# board.net
KiCad netlist of a schematic drawn in EAGLE
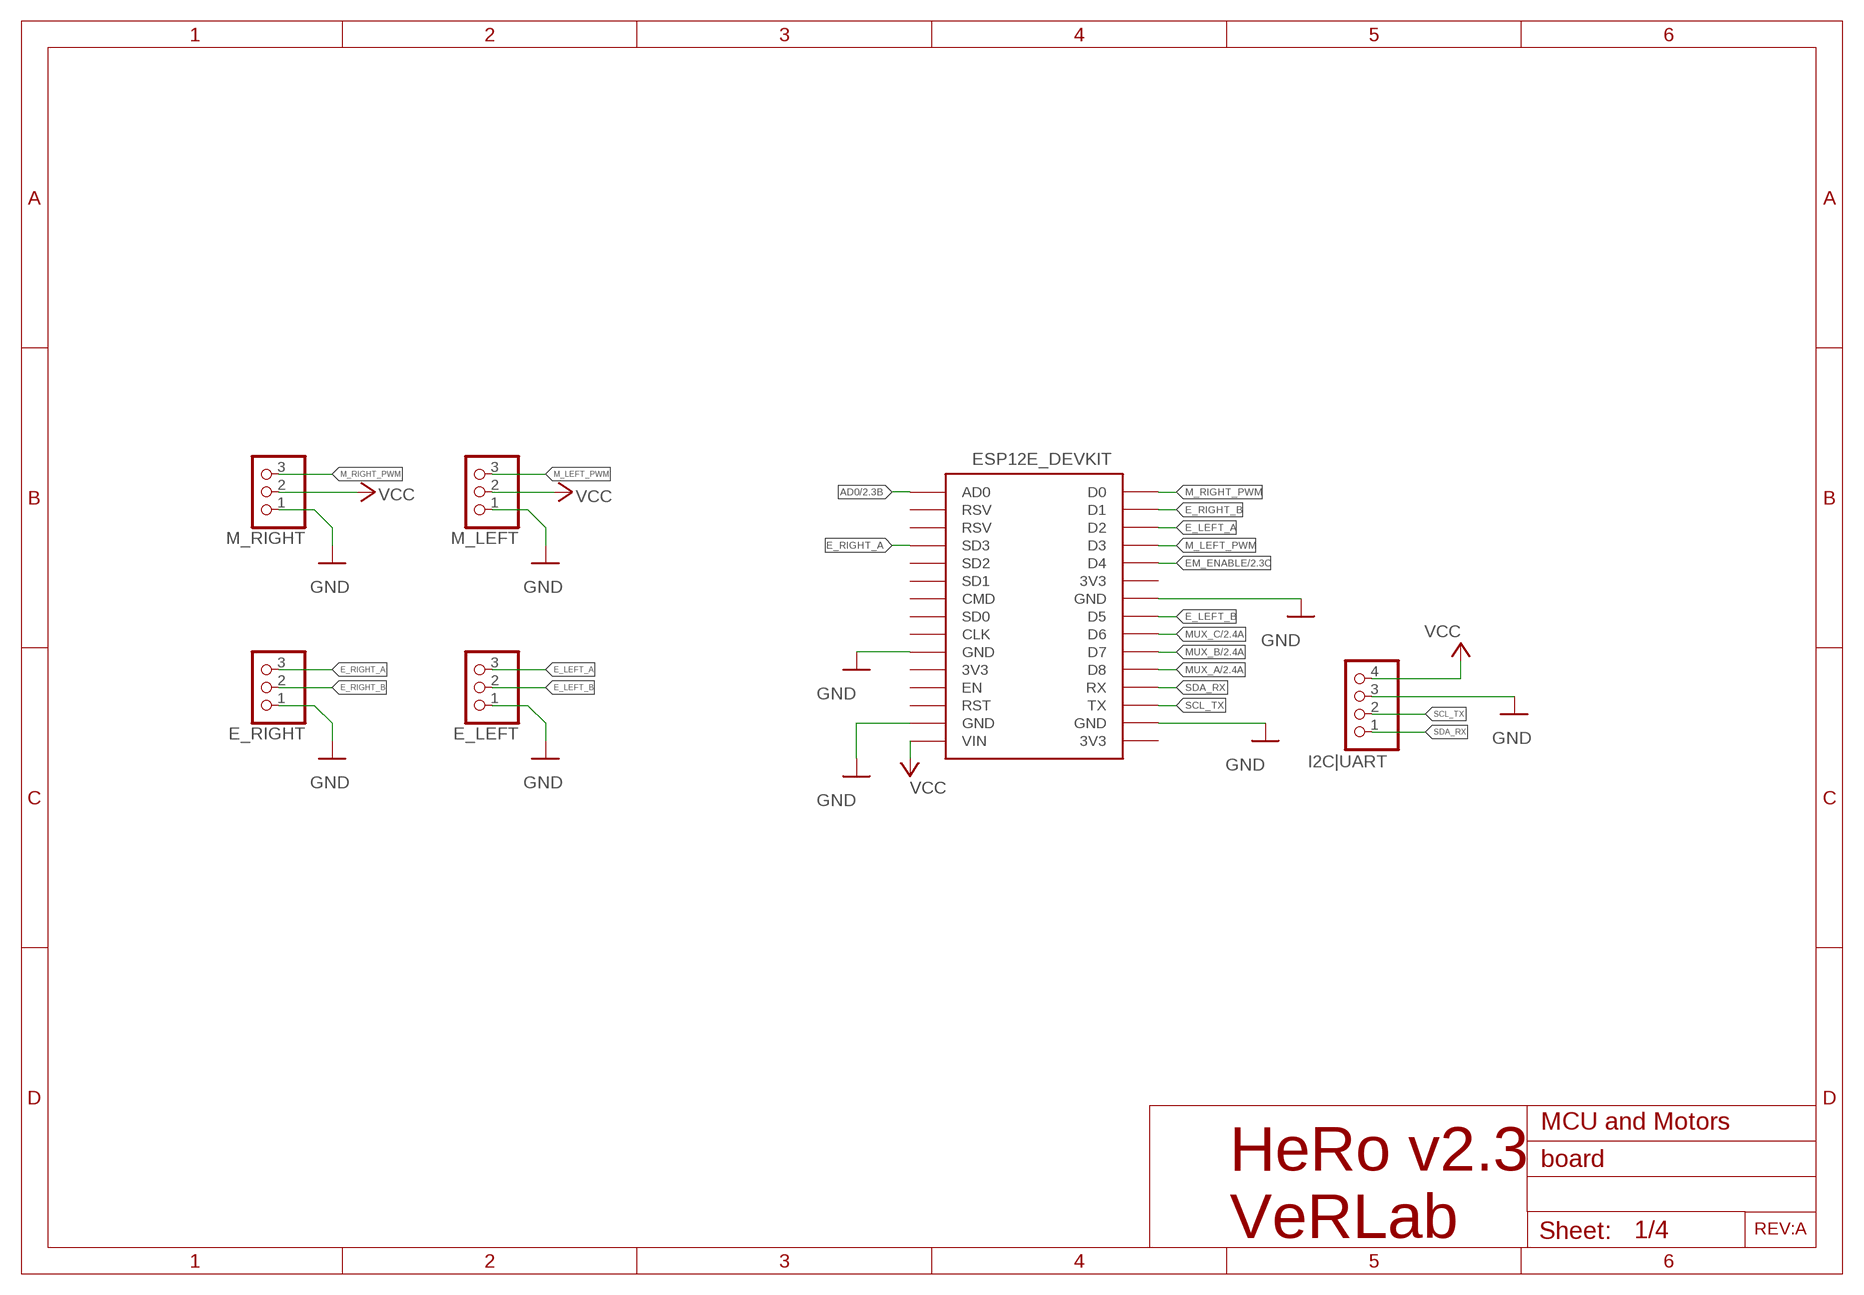
[diagram p0: schematic, sheet 1]
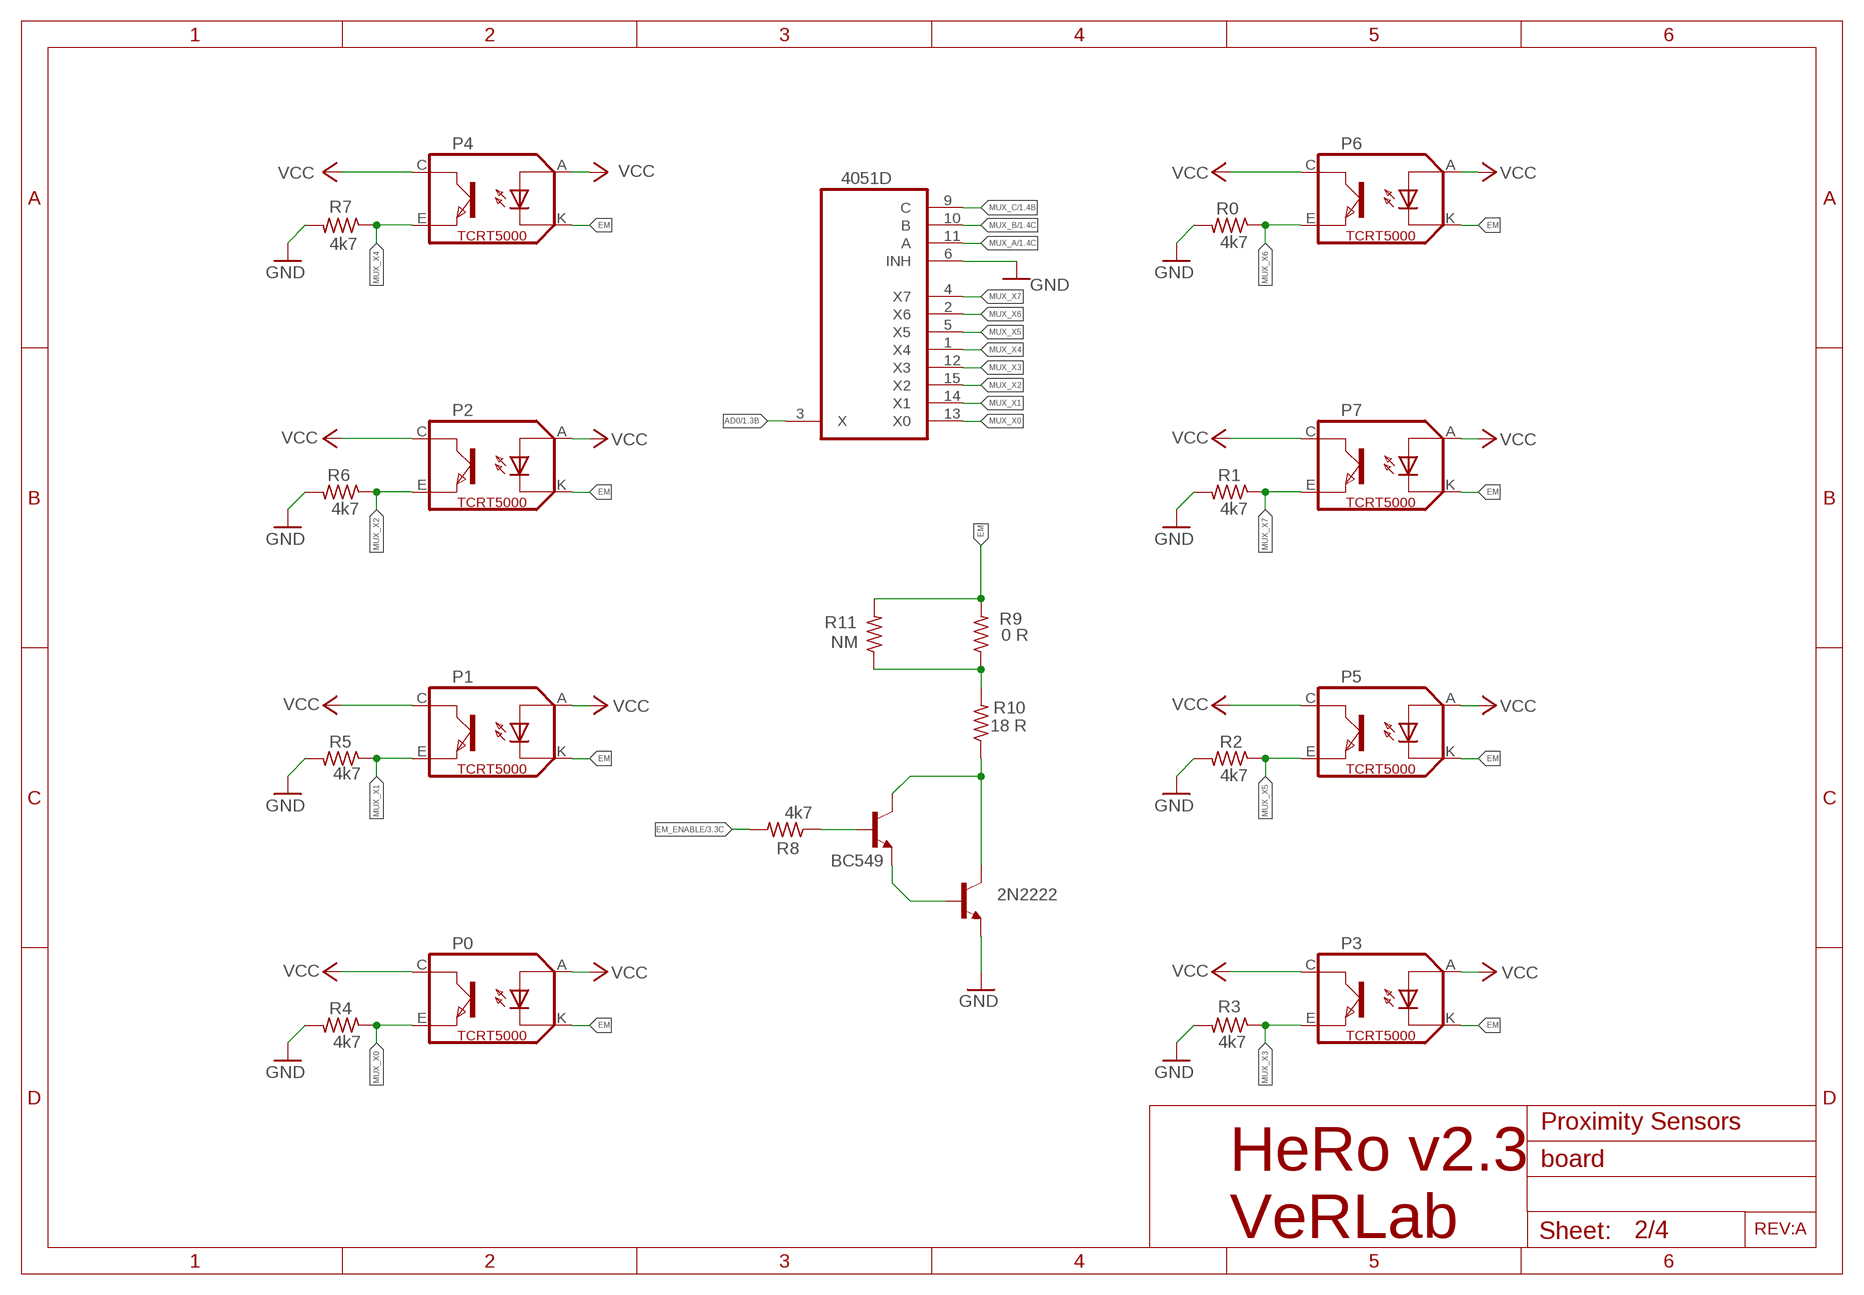
[diagram p1: schematic, sheet 2]
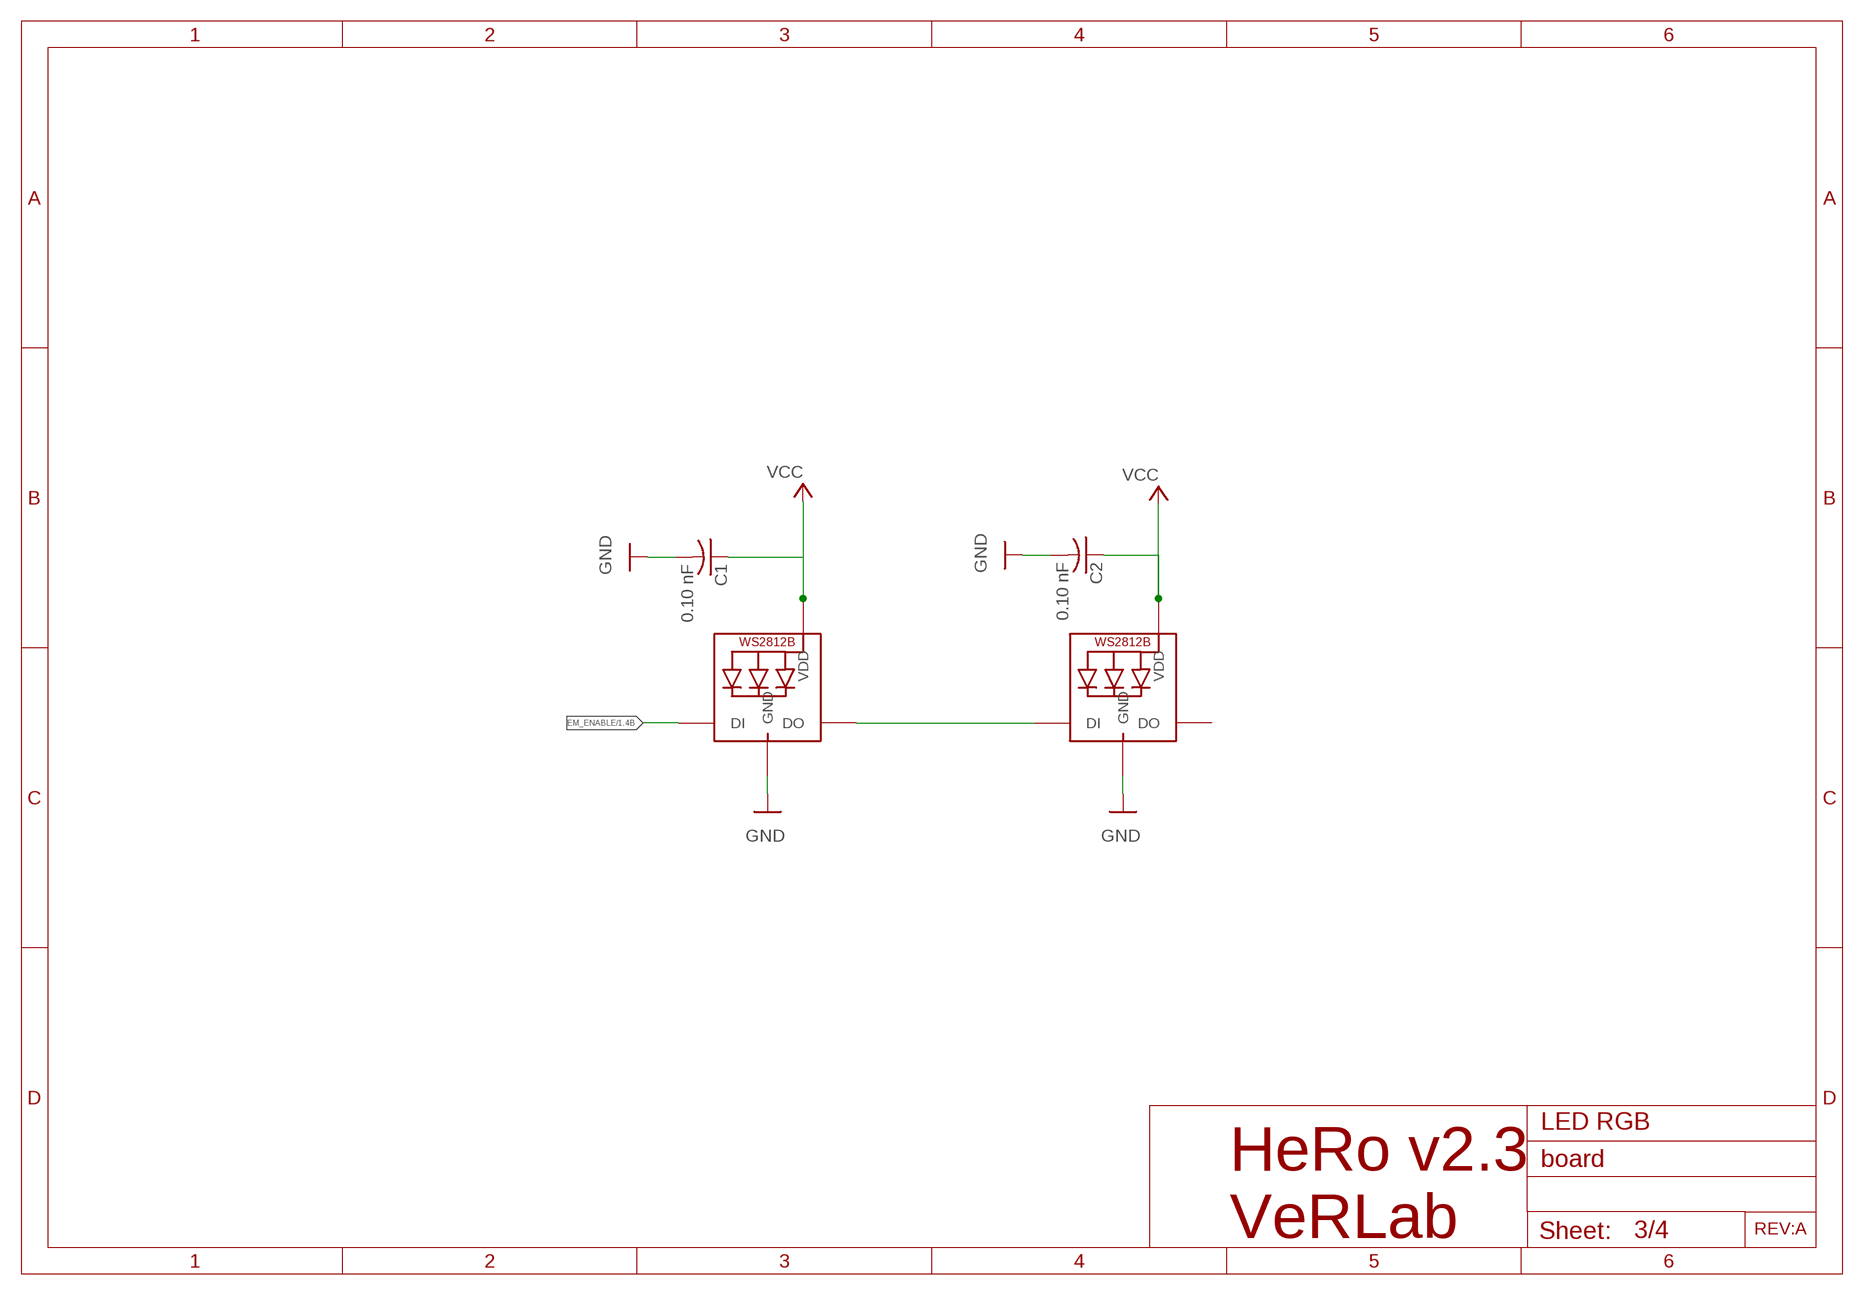
[diagram p2: schematic, sheet 3]
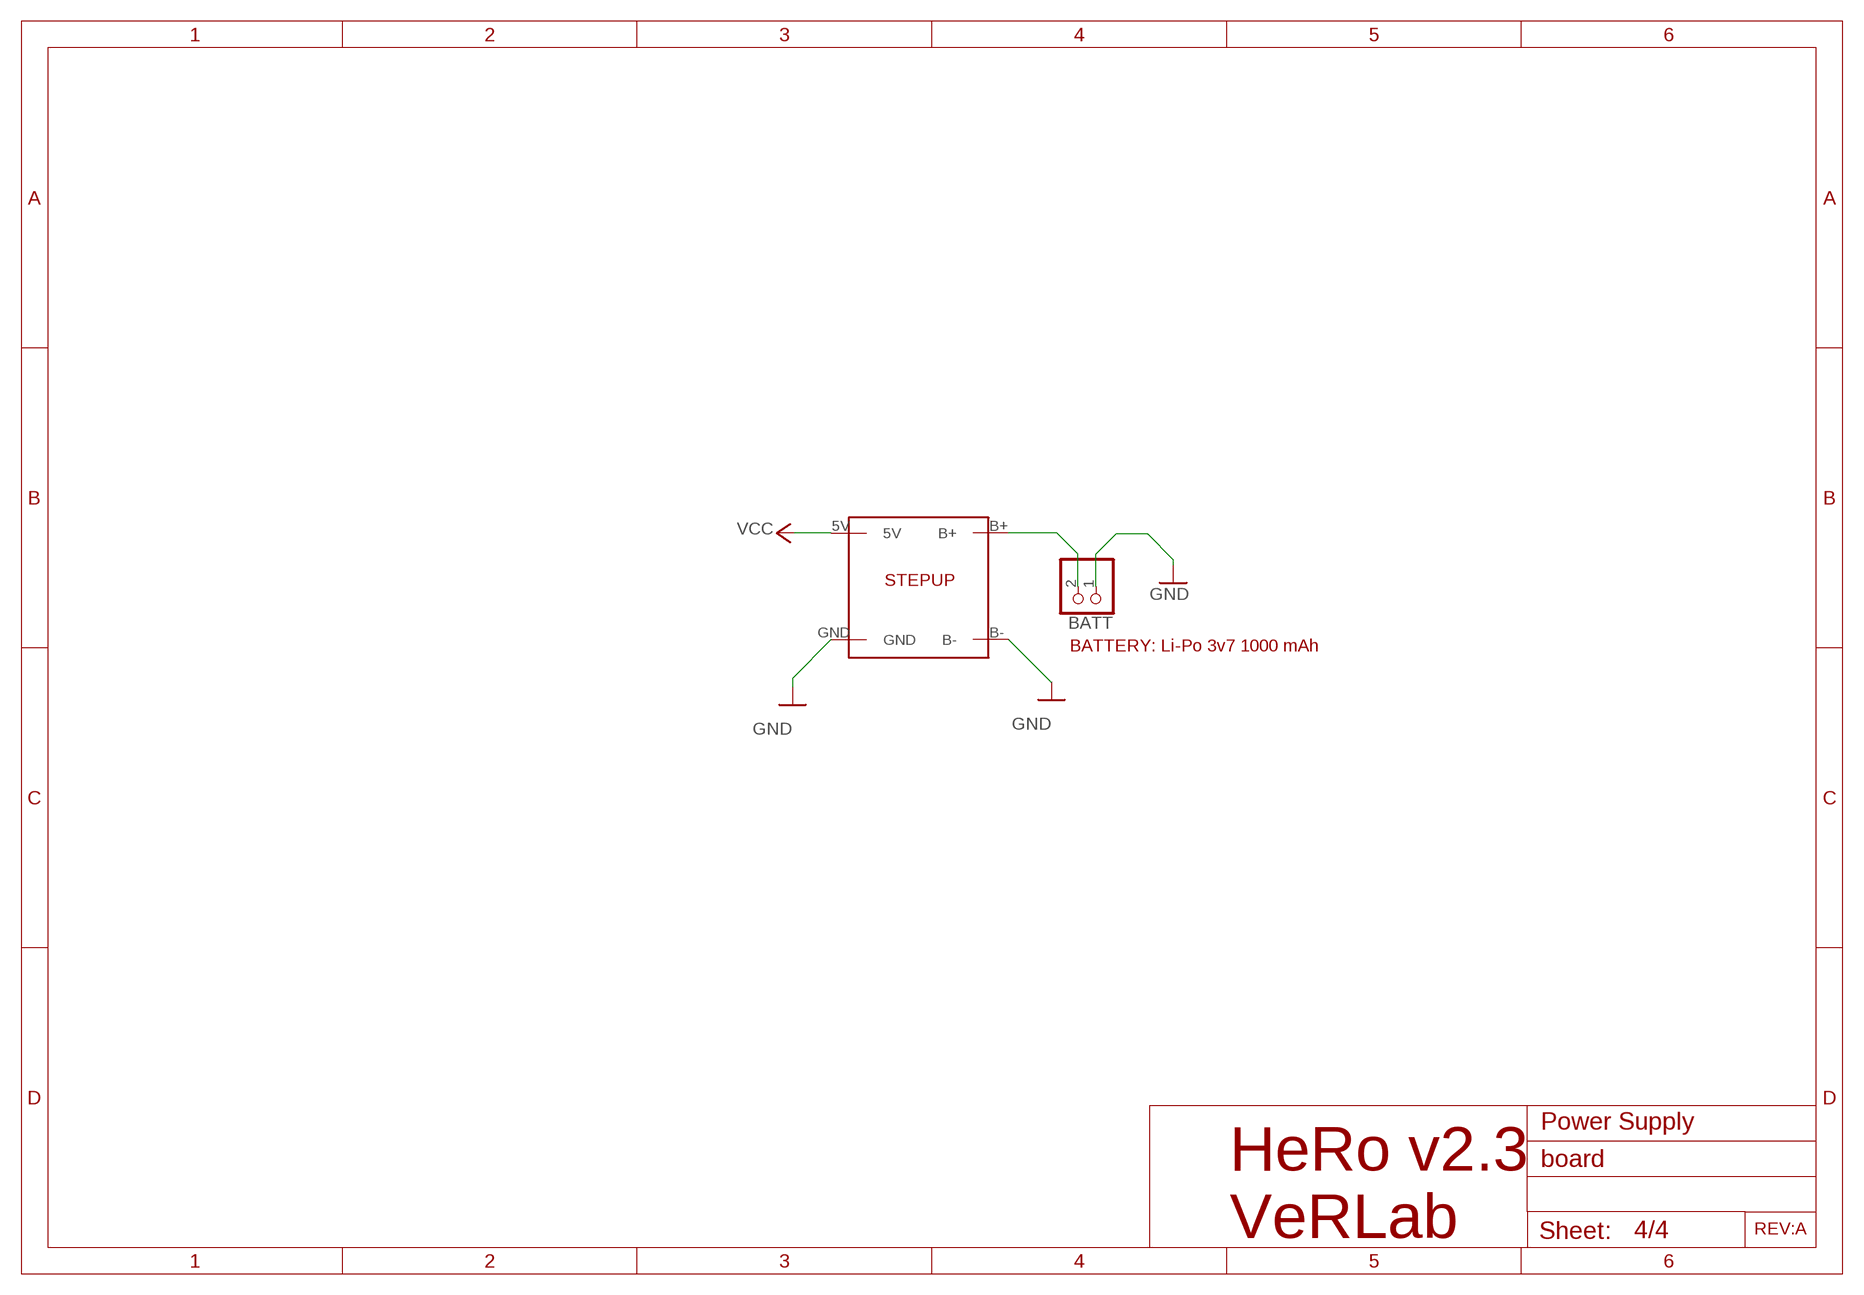
[diagram p3: schematic, sheet 4]

(export (version "E")
  (design (tool "Eeschema 10.0.6"))
  (components
    (comp (ref "E_LEFT")
      (value "PINHD-1X3")
      (footprint "eagle-import:1X03")
      (libsource (lib "eagle-import") (part "PINHD-1X3"))
    )
    (comp (ref "E_RIGHT")
      (value "PINHD-1X3")
      (footprint "eagle-import:1X03")
      (libsource (lib "eagle-import") (part "PINHD-1X3"))
    )
    (comp (ref "I2C|UART")
      (value "PINHD-1X4")
      (footprint "eagle-import:1X04")
      (libsource (lib "eagle-import") (part "PINHD-1X4"))
    )
    (comp (ref "M_LEFT")
      (value "PINHD-1X3")
      (footprint "eagle-import:1X03")
      (libsource (lib "eagle-import") (part "PINHD-1X3"))
    )
    (comp (ref "M_RIGHT")
      (value "PINHD-1X3")
      (footprint "eagle-import:1X03")
      (libsource (lib "eagle-import") (part "PINHD-1X3"))
    )
    (comp (ref "U$1")
      (value "ESP12E_DEVKIT")
      (footprint "eagle-import:ESP12E_DEVKIT")
      (libsource (lib "eagle-import") (part "ESP12E_DEVKIT"))
    )
    (comp (ref "C1")
      (value "0.10 nF")
      (footprint "eagle-import:C0603")
      (libsource (lib "eagle-import") (part "C-USC0603"))
    )
    (comp (ref "C2")
      (value "0.10 nF")
      (footprint "eagle-import:C0603")
      (libsource (lib "eagle-import") (part "C-USC0603"))
    )
    (comp (ref "LED3")
      (value "WS2812B5050")
      (footprint "eagle-import:WS2812B")
      (libsource (lib "eagle-import") (part "WS2812B5050"))
    )
    (comp (ref "LED4")
      (value "WS2812B5050")
      (footprint "eagle-import:WS2812B")
      (libsource (lib "eagle-import") (part "WS2812B5050"))
    )
    (comp (ref "BATT")
      (value "PINHD-1X2")
      (footprint "eagle-import:1X02")
      (libsource (lib "eagle-import") (part "PINHD-1X2"))
    )
    (comp (ref "OS1")
      (value "STEPUP")
      (footprint "eagle-import:STEPUP")
      (libsource (lib "eagle-import") (part "STEPUP"))
    )
    (comp (ref "BC549")
      (value "BC549-NPN-TO92-CBE")
      (footprint "eagle-import:TO92-CBE")
      (fields (field (name "SPICEPREFIX") "J"))
      (libsource (lib "eagle-import") (part "-NPN-TO92-CBEBC549"))
    )
    (comp (ref "IC2")
      (value "4051D")
      (footprint "eagle-import:SO16")
      (libsource (lib "eagle-import") (part "4051D"))
    )
    (comp (ref "P0")
      (value "TCRT5000")
      (footprint "eagle-import:TCRT5000")
      (libsource (lib "eagle-import") (part "TCRT5000"))
    )
    (comp (ref "P1")
      (value "TCRT5000")
      (footprint "eagle-import:TCRT5000")
      (libsource (lib "eagle-import") (part "TCRT5000"))
    )
    (comp (ref "P2")
      (value "TCRT5000")
      (footprint "eagle-import:TCRT5000")
      (libsource (lib "eagle-import") (part "TCRT5000"))
    )
    (comp (ref "P3")
      (value "TCRT5000")
      (footprint "eagle-import:TCRT5000")
      (libsource (lib "eagle-import") (part "TCRT5000"))
    )
    (comp (ref "P4")
      (value "TCRT5000")
      (footprint "eagle-import:TCRT5000")
      (libsource (lib "eagle-import") (part "TCRT5000"))
    )
    (comp (ref "P5")
      (value "TCRT5000")
      (footprint "eagle-import:TCRT5000")
      (libsource (lib "eagle-import") (part "TCRT5000"))
    )
    (comp (ref "P6")
      (value "TCRT5000")
      (footprint "eagle-import:TCRT5000")
      (libsource (lib "eagle-import") (part "TCRT5000"))
    )
    (comp (ref "P7")
      (value "TCRT5000")
      (footprint "eagle-import:TCRT5000")
      (libsource (lib "eagle-import") (part "TCRT5000"))
    )
    (comp (ref "R0")
      (value "4k7")
      (footprint "eagle-import:M0805")
      (libsource (lib "eagle-import") (part "R-US_M0805"))
    )
    (comp (ref "R1")
      (value "4k7")
      (footprint "eagle-import:M0805")
      (libsource (lib "eagle-import") (part "R-US_M0805"))
    )
    (comp (ref "R2")
      (value "4k7")
      (footprint "eagle-import:M0805")
      (libsource (lib "eagle-import") (part "R-US_M0805"))
    )
    (comp (ref "R3")
      (value "4k7")
      (footprint "eagle-import:M0805")
      (libsource (lib "eagle-import") (part "R-US_M0805"))
    )
    (comp (ref "R4")
      (value "4k7")
      (footprint "eagle-import:M0805")
      (libsource (lib "eagle-import") (part "R-US_M0805"))
    )
    (comp (ref "R5")
      (value "4k7")
      (footprint "eagle-import:M0805")
      (libsource (lib "eagle-import") (part "R-US_M0805"))
    )
    (comp (ref "R6")
      (value "4k7")
      (footprint "eagle-import:M0805")
      (libsource (lib "eagle-import") (part "R-US_M0805"))
    )
    (comp (ref "R7")
      (value "4k7")
      (footprint "eagle-import:M0805")
      (libsource (lib "eagle-import") (part "R-US_M0805"))
    )
    (comp (ref "R8")
      (value "4k7")
      (footprint "eagle-import:R0805")
      (fields (field (name "SPICEPREFIX") "R"))
      (libsource (lib "eagle-import") (part "resistor_348_R-US_R0805"))
    )
    (comp (ref "R9")
      (value "0 R")
      (footprint "eagle-import:R0805")
      (fields (field (name "SPICEPREFIX") "R"))
      (libsource (lib "eagle-import") (part "resistor_348_R-US_R0805"))
    )
    (comp (ref "R10")
      (value "18 R")
      (footprint "eagle-import:R0805")
      (fields (field (name "SPICEPREFIX") "R"))
      (libsource (lib "eagle-import") (part "resistor_348_R-US_R0805"))
    )
    (comp (ref "R11")
      (value "NM")
      (footprint "eagle-import:R0805")
      (fields (field (name "SPICEPREFIX") "R"))
      (libsource (lib "eagle-import") (part "resistor_348_R-US_R0805"))
    )
    (comp (ref "T5")
      (value "2N2222")
      (footprint "eagle-import:TO92-EBC-OVAL")
      (fields (field (name "SPICEPREFIX") "J"))
      (libsource (lib "eagle-import") (part "2N2222"))
    )
  )
  (nets
    (net (code "1") (name "AD0") (class "Default")
      (node (ref "IC2") (pin "3") (pinfunction "X_3") (pintype "bidirectional"))
      (node (ref "U$1") (pin "AD0") (pinfunction "AD0_AD0") (pintype "bidirectional"))
    )
    (net (code "2") (name "EM") (class "Default")
      (node (ref "P0") (pin "K") (pinfunction "CATHODE_K") (pintype "passive"))
      (node (ref "P1") (pin "K") (pinfunction "CATHODE_K") (pintype "passive"))
      (node (ref "P2") (pin "K") (pinfunction "CATHODE_K") (pintype "passive"))
      (node (ref "P3") (pin "K") (pinfunction "CATHODE_K") (pintype "passive"))
      (node (ref "P4") (pin "K") (pinfunction "CATHODE_K") (pintype "passive"))
      (node (ref "P5") (pin "K") (pinfunction "CATHODE_K") (pintype "passive"))
      (node (ref "P6") (pin "K") (pinfunction "CATHODE_K") (pintype "passive"))
      (node (ref "P7") (pin "K") (pinfunction "CATHODE_K") (pintype "passive"))
      (node (ref "R11") (pin "2") (pinfunction "2_2") (pintype "passive"))
      (node (ref "R9") (pin "2") (pinfunction "2_2") (pintype "passive"))
    )
    (net (code "3") (name "EM_ENABLE") (class "Default")
      (node (ref "LED3") (pin "4-DIN") (pinfunction "DI_4-DIN") (pintype "input"))
      (node (ref "R8") (pin "2") (pinfunction "2_2") (pintype "passive"))
      (node (ref "U$1") (pin "D4") (pinfunction "D4_D4") (pintype "bidirectional"))
    )
    (net (code "4") (name "E_LEFT_A") (class "Default")
      (node (ref "E_LEFT") (pin "3") (pinfunction "3_3") (pintype "passive"))
      (node (ref "U$1") (pin "D2") (pinfunction "D2_D2") (pintype "bidirectional"))
    )
    (net (code "5") (name "E_LEFT_B") (class "Default")
      (node (ref "E_LEFT") (pin "2") (pinfunction "2_2") (pintype "passive"))
      (node (ref "U$1") (pin "D5") (pinfunction "D5_D5") (pintype "bidirectional"))
    )
    (net (code "6") (name "E_RIGHT_A") (class "Default")
      (node (ref "E_RIGHT") (pin "3") (pinfunction "3_3") (pintype "passive"))
      (node (ref "U$1") (pin "SD3") (pinfunction "SD3_SD3") (pintype "bidirectional"))
    )
    (net (code "7") (name "E_RIGHT_B") (class "Default")
      (node (ref "E_RIGHT") (pin "2") (pinfunction "2_2") (pintype "passive"))
      (node (ref "U$1") (pin "D1") (pinfunction "D1_D1") (pintype "bidirectional"))
    )
    (net (code "8") (name "GND") (class "Default")
      (node (ref "BATT") (pin "1") (pinfunction "1_1") (pintype "passive"))
      (node (ref "C1") (pin "2") (pinfunction "2_2") (pintype "passive"))
      (node (ref "C2") (pin "2") (pinfunction "2_2") (pintype "passive"))
      (node (ref "E_LEFT") (pin "1") (pinfunction "1_1") (pintype "passive"))
      (node (ref "E_RIGHT") (pin "1") (pinfunction "1_1") (pintype "passive"))
      (node (ref "I2C|UART") (pin "3") (pinfunction "3_3") (pintype "passive"))
      (node (ref "IC2") (pin "6") (pinfunction "INH_6") (pintype "input"))
      (node (ref "LED3") (pin "3-GND") (pinfunction "GND_3-GND") (pintype "power_in"))
      (node (ref "LED4") (pin "3-GND") (pinfunction "GND_3-GND") (pintype "power_in"))
      (node (ref "M_LEFT") (pin "1") (pinfunction "1_1") (pintype "passive"))
      (node (ref "M_RIGHT") (pin "1") (pinfunction "1_1") (pintype "passive"))
      (node (ref "OS1") (pin "B-") (pinfunction "B-_B-") (pintype "input"))
      (node (ref "OS1") (pin "GND") (pinfunction "GND_GND") (pintype "output"))
      (node (ref "R0") (pin "2") (pinfunction "2_2") (pintype "passive"))
      (node (ref "R1") (pin "2") (pinfunction "2_2") (pintype "passive"))
      (node (ref "R2") (pin "2") (pinfunction "2_2") (pintype "passive"))
      (node (ref "R3") (pin "2") (pinfunction "2_2") (pintype "passive"))
      (node (ref "R4") (pin "2") (pinfunction "2_2") (pintype "passive"))
      (node (ref "R5") (pin "2") (pinfunction "2_2") (pintype "passive"))
      (node (ref "R6") (pin "2") (pinfunction "2_2") (pintype "passive"))
      (node (ref "R7") (pin "2") (pinfunction "2_2") (pintype "passive"))
      (node (ref "T5") (pin "E") (pinfunction "E_E") (pintype "passive"))
      (node (ref "U$1") (pin "GND@0") (pinfunction "GND_GND@0") (pintype "bidirectional"))
      (node (ref "U$1") (pin "GND@1") (pinfunction "GND_GND@1") (pintype "bidirectional"))
      (node (ref "U$1") (pin "GND@2") (pinfunction "GND_GND@2") (pintype "bidirectional"))
      (node (ref "U$1") (pin "GND@3") (pinfunction "GND_GND@3") (pintype "bidirectional"))
    )
    (net (code "9") (name "MUX_A") (class "Default")
      (node (ref "IC2") (pin "11") (pinfunction "A_11") (pintype "input"))
      (node (ref "U$1") (pin "D8") (pinfunction "D8_D8") (pintype "bidirectional"))
    )
    (net (code "10") (name "MUX_B") (class "Default")
      (node (ref "IC2") (pin "10") (pinfunction "B_10") (pintype "input"))
      (node (ref "U$1") (pin "D7") (pinfunction "D7_D7") (pintype "bidirectional"))
    )
    (net (code "11") (name "MUX_C") (class "Default")
      (node (ref "IC2") (pin "9") (pinfunction "C_9") (pintype "input"))
      (node (ref "U$1") (pin "D6") (pinfunction "D6_D6") (pintype "bidirectional"))
    )
    (net (code "12") (name "MUX_X0") (class "Default")
      (node (ref "IC2") (pin "13") (pinfunction "X0_13") (pintype "bidirectional"))
      (node (ref "P0") (pin "E") (pinfunction "EMITTER_E") (pintype "passive"))
      (node (ref "R4") (pin "1") (pinfunction "1_1") (pintype "passive"))
    )
    (net (code "13") (name "MUX_X1") (class "Default")
      (node (ref "IC2") (pin "14") (pinfunction "X1_14") (pintype "bidirectional"))
      (node (ref "P1") (pin "E") (pinfunction "EMITTER_E") (pintype "passive"))
      (node (ref "R5") (pin "1") (pinfunction "1_1") (pintype "passive"))
    )
    (net (code "14") (name "MUX_X2") (class "Default")
      (node (ref "IC2") (pin "15") (pinfunction "X2_15") (pintype "bidirectional"))
      (node (ref "P2") (pin "E") (pinfunction "EMITTER_E") (pintype "passive"))
      (node (ref "R6") (pin "1") (pinfunction "1_1") (pintype "passive"))
    )
    (net (code "15") (name "MUX_X3") (class "Default")
      (node (ref "IC2") (pin "12") (pinfunction "X3_12") (pintype "bidirectional"))
      (node (ref "P3") (pin "E") (pinfunction "EMITTER_E") (pintype "passive"))
      (node (ref "R3") (pin "1") (pinfunction "1_1") (pintype "passive"))
    )
    (net (code "16") (name "MUX_X4") (class "Default")
      (node (ref "IC2") (pin "1") (pinfunction "X4_1") (pintype "bidirectional"))
      (node (ref "P4") (pin "E") (pinfunction "EMITTER_E") (pintype "passive"))
      (node (ref "R7") (pin "1") (pinfunction "1_1") (pintype "passive"))
    )
    (net (code "17") (name "MUX_X5") (class "Default")
      (node (ref "IC2") (pin "5") (pinfunction "X5_5") (pintype "bidirectional"))
      (node (ref "P5") (pin "E") (pinfunction "EMITTER_E") (pintype "passive"))
      (node (ref "R2") (pin "1") (pinfunction "1_1") (pintype "passive"))
    )
    (net (code "18") (name "MUX_X6") (class "Default")
      (node (ref "IC2") (pin "2") (pinfunction "X6_2") (pintype "bidirectional"))
      (node (ref "P6") (pin "E") (pinfunction "EMITTER_E") (pintype "passive"))
      (node (ref "R0") (pin "1") (pinfunction "1_1") (pintype "passive"))
    )
    (net (code "19") (name "MUX_X7") (class "Default")
      (node (ref "IC2") (pin "4") (pinfunction "X7_4") (pintype "bidirectional"))
      (node (ref "P7") (pin "E") (pinfunction "EMITTER_E") (pintype "passive"))
      (node (ref "R1") (pin "1") (pinfunction "1_1") (pintype "passive"))
    )
    (net (code "20") (name "M_LEFT_PWM") (class "Default")
      (node (ref "M_LEFT") (pin "3") (pinfunction "3_3") (pintype "passive"))
      (node (ref "U$1") (pin "D3") (pinfunction "D3_D3") (pintype "bidirectional"))
    )
    (net (code "21") (name "M_RIGHT_PWM") (class "Default")
      (node (ref "M_RIGHT") (pin "3") (pinfunction "3_3") (pintype "passive"))
      (node (ref "U$1") (pin "D0") (pinfunction "D0_D0") (pintype "bidirectional"))
    )
    (net (code "22") (name "Net-(BATT-Pad2)") (class "Default")
      (node (ref "BATT") (pin "2") (pinfunction "2_2") (pintype "passive"))
      (node (ref "OS1") (pin "B+") (pinfunction "B+_B+") (pintype "input"))
    )
    (net (code "23") (name "Net-(BC549-PadB)") (class "Default")
      (node (ref "BC549") (pin "B") (pinfunction "B_B") (pintype "passive"))
      (node (ref "R8") (pin "1") (pinfunction "1_1") (pintype "passive"))
    )
    (net (code "24") (name "Net-(BC549-PadC)") (class "Default")
      (node (ref "BC549") (pin "C") (pinfunction "C_C") (pintype "passive"))
      (node (ref "R10") (pin "1") (pinfunction "1_1") (pintype "passive"))
      (node (ref "T5") (pin "C") (pinfunction "C_C") (pintype "passive"))
    )
    (net (code "25") (name "Net-(BC549-PadE)") (class "Default")
      (node (ref "BC549") (pin "E") (pinfunction "E_E") (pintype "passive"))
      (node (ref "T5") (pin "B") (pinfunction "B_B") (pintype "passive"))
    )
    (net (code "26") (name "Net-(LED3-DO)") (class "Default")
      (node (ref "LED3") (pin "2-DOUT") (pinfunction "DO_2-DOUT") (pintype "output"))
      (node (ref "LED4") (pin "4-DIN") (pinfunction "DI_4-DIN") (pintype "input"))
    )
    (net (code "27") (name "Net-(R10-Pad2)") (class "Default")
      (node (ref "R10") (pin "2") (pinfunction "2_2") (pintype "passive"))
      (node (ref "R11") (pin "1") (pinfunction "1_1") (pintype "passive"))
      (node (ref "R9") (pin "1") (pinfunction "1_1") (pintype "passive"))
    )
    (net (code "28") (name "SCL_TX") (class "Default")
      (node (ref "I2C|UART") (pin "2") (pinfunction "2_2") (pintype "passive"))
      (node (ref "U$1") (pin "TX") (pinfunction "TX_TX") (pintype "bidirectional"))
    )
    (net (code "29") (name "SDA_RX") (class "Default")
      (node (ref "I2C|UART") (pin "1") (pinfunction "1_1") (pintype "passive"))
      (node (ref "U$1") (pin "RX") (pinfunction "RX_RX") (pintype "bidirectional"))
    )
    (net (code "30") (name "VCC") (class "Default")
      (node (ref "C1") (pin "1") (pinfunction "1_1") (pintype "passive"))
      (node (ref "C2") (pin "1") (pinfunction "1_1") (pintype "passive"))
      (node (ref "I2C|UART") (pin "4") (pinfunction "4_4") (pintype "passive"))
      (node (ref "LED3") (pin "1-VDD") (pinfunction "VDD_1-VDD") (pintype "power_in"))
      (node (ref "LED4") (pin "1-VDD") (pinfunction "VDD_1-VDD") (pintype "power_in"))
      (node (ref "M_LEFT") (pin "2") (pinfunction "2_2") (pintype "passive"))
      (node (ref "M_RIGHT") (pin "2") (pinfunction "2_2") (pintype "passive"))
      (node (ref "OS1") (pin "5V") (pinfunction "5V_5V") (pintype "output"))
      (node (ref "P0") (pin "A") (pinfunction "ANODE_A") (pintype "passive"))
      (node (ref "P0") (pin "C") (pinfunction "COLLECTOR_C") (pintype "passive"))
      (node (ref "P1") (pin "A") (pinfunction "ANODE_A") (pintype "passive"))
      (node (ref "P1") (pin "C") (pinfunction "COLLECTOR_C") (pintype "passive"))
      (node (ref "P2") (pin "A") (pinfunction "ANODE_A") (pintype "passive"))
      (node (ref "P2") (pin "C") (pinfunction "COLLECTOR_C") (pintype "passive"))
      (node (ref "P3") (pin "A") (pinfunction "ANODE_A") (pintype "passive"))
      (node (ref "P3") (pin "C") (pinfunction "COLLECTOR_C") (pintype "passive"))
      (node (ref "P4") (pin "A") (pinfunction "ANODE_A") (pintype "passive"))
      (node (ref "P4") (pin "C") (pinfunction "COLLECTOR_C") (pintype "passive"))
      (node (ref "P5") (pin "A") (pinfunction "ANODE_A") (pintype "passive"))
      (node (ref "P5") (pin "C") (pinfunction "COLLECTOR_C") (pintype "passive"))
      (node (ref "P6") (pin "A") (pinfunction "ANODE_A") (pintype "passive"))
      (node (ref "P6") (pin "C") (pinfunction "COLLECTOR_C") (pintype "passive"))
      (node (ref "P7") (pin "A") (pinfunction "ANODE_A") (pintype "passive"))
      (node (ref "P7") (pin "C") (pinfunction "COLLECTOR_C") (pintype "passive"))
      (node (ref "U$1") (pin "VIN") (pinfunction "VIN_VIN") (pintype "bidirectional"))
    )
    (net (code "31") (name "unconnected-(LED4-DO-Pad2-DOUT)") (class "Default")
      (node (ref "LED4") (pin "2-DOUT") (pinfunction "DO_2-DOUT") (pintype "output"))
    )
    (net (code "32") (name "unconnected-(U$1-3V3-Pad3V3@0)") (class "Default")
      (node (ref "U$1") (pin "3V3@0") (pinfunction "3V3_3V3@0") (pintype "bidirectional"))
    )
    (net (code "33") (name "unconnected-(U$1-3V3-Pad3V3@1)") (class "Default")
      (node (ref "U$1") (pin "3V3@1") (pinfunction "3V3_3V3@1") (pintype "bidirectional"))
    )
    (net (code "34") (name "unconnected-(U$1-3V3-Pad3V3@2)") (class "Default")
      (node (ref "U$1") (pin "3V3@2") (pinfunction "3V3_3V3@2") (pintype "bidirectional"))
    )
    (net (code "35") (name "unconnected-(U$1-PadCLK)") (class "Default")
      (node (ref "U$1") (pin "CLK") (pinfunction "CLK_CLK") (pintype "bidirectional"))
    )
    (net (code "36") (name "unconnected-(U$1-PadCMD)") (class "Default")
      (node (ref "U$1") (pin "CMD") (pinfunction "CMD_CMD") (pintype "bidirectional"))
    )
    (net (code "37") (name "unconnected-(U$1-PadEN)") (class "Default")
      (node (ref "U$1") (pin "EN") (pinfunction "EN_EN") (pintype "bidirectional"))
    )
    (net (code "38") (name "unconnected-(U$1-PadRST)") (class "Default")
      (node (ref "U$1") (pin "RST") (pinfunction "RST_RST") (pintype "bidirectional"))
    )
    (net (code "39") (name "unconnected-(U$1-PadSD0)") (class "Default")
      (node (ref "U$1") (pin "SD0") (pinfunction "SD0_SD0") (pintype "bidirectional"))
    )
    (net (code "40") (name "unconnected-(U$1-PadSD1)") (class "Default")
      (node (ref "U$1") (pin "SD1") (pinfunction "SD1_SD1") (pintype "bidirectional"))
    )
    (net (code "41") (name "unconnected-(U$1-PadSD2)") (class "Default")
      (node (ref "U$1") (pin "SD2") (pinfunction "SD2_SD2") (pintype "bidirectional"))
    )
    (net (code "42") (name "unconnected-(U$1-RSV-PadRSV@0)") (class "Default")
      (node (ref "U$1") (pin "RSV@0") (pinfunction "RSV_RSV@0") (pintype "bidirectional"))
    )
    (net (code "43") (name "unconnected-(U$1-RSV-PadRSV@1)") (class "Default")
      (node (ref "U$1") (pin "RSV@1") (pinfunction "RSV_RSV@1") (pintype "bidirectional"))
    )
  )
)
